# FET-module.net
KiCad netlist of a schematic drawn in Altium Designer
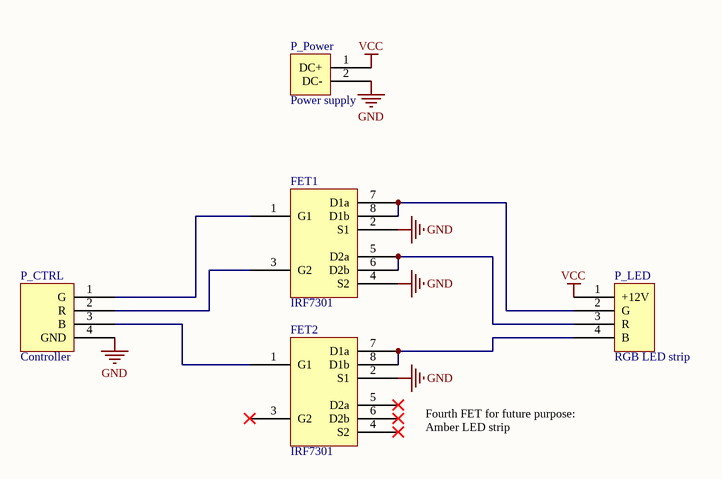
[diagram p0: FET-module.SchDoc]

(export (version "E")
  (design (tool "Eeschema 10.0.6"))
  (components
    (comp (ref "FET1") (value "IRF7301") (footprint "SOIC8") (libsource (lib "FET-module") (part "IRF7301")))
    (comp (ref "FET2") (value "IRF7301") (footprint "SOIC8") (libsource (lib "FET-module") (part "IRF7301")))
    (comp (ref "P_CTRL")
      (value "Controller")
      (footprint "Controller connector")
      (libsource (lib "FET-module") (part "Controller"))
    )
    (comp (ref "P_LED")
      (value "RGB LED strip")
      (footprint "LED strip RGB connector")
      (libsource (lib "FET-module") (part "RGB LED strip"))
    )
    (comp (ref "P_Power")
      (value "Power supply")
      (footprint "DC connector")
      (libsource (lib "FET-module") (part "Power supply"))
    )
  )
  (nets
    (net (code "1") (name "GND") (class "Default")
      (node (ref "FET1") (pin "2") (pinfunction "S1_2") (pintype "passive"))
      (node (ref "FET1") (pin "4") (pinfunction "S2_4") (pintype "passive"))
      (node (ref "FET2") (pin "2") (pinfunction "S1_2") (pintype "passive"))
      (node (ref "P_CTRL") (pin "4") (pinfunction "GND_4") (pintype "passive"))
      (node (ref "P_Power") (pin "2") (pinfunction "DC-_2") (pintype "passive"))
    )
    (net (code "2") (name "Net-(FET1-D1a)") (class "Default")
      (node (ref "FET1") (pin "7") (pinfunction "D1a_7") (pintype "passive"))
      (node (ref "FET1") (pin "8") (pinfunction "D1b_8") (pintype "passive"))
      (node (ref "P_LED") (pin "2") (pinfunction "G_2") (pintype "passive"))
    )
    (net (code "3") (name "Net-(FET1-D2a)") (class "Default")
      (node (ref "FET1") (pin "5") (pinfunction "D2a_5") (pintype "passive"))
      (node (ref "FET1") (pin "6") (pinfunction "D2b_6") (pintype "passive"))
      (node (ref "P_LED") (pin "3") (pinfunction "R_3") (pintype "passive"))
    )
    (net (code "4") (name "Net-(FET1-G1)") (class "Default")
      (node (ref "FET1") (pin "1") (pinfunction "G1_1") (pintype "passive"))
      (node (ref "P_CTRL") (pin "1") (pinfunction "G_1") (pintype "passive"))
    )
    (net (code "5") (name "Net-(FET1-G2)") (class "Default")
      (node (ref "FET1") (pin "3") (pinfunction "G2_3") (pintype "passive"))
      (node (ref "P_CTRL") (pin "2") (pinfunction "R_2") (pintype "passive"))
    )
    (net (code "6") (name "Net-(FET2-D1a)") (class "Default")
      (node (ref "FET2") (pin "7") (pinfunction "D1a_7") (pintype "passive"))
      (node (ref "FET2") (pin "8") (pinfunction "D1b_8") (pintype "passive"))
      (node (ref "P_LED") (pin "4") (pinfunction "B_4") (pintype "passive"))
    )
    (net (code "7") (name "Net-(FET2-G1)") (class "Default")
      (node (ref "FET2") (pin "1") (pinfunction "G1_1") (pintype "passive"))
      (node (ref "P_CTRL") (pin "3") (pinfunction "B_3") (pintype "passive"))
    )
    (net (code "8") (name "VCC") (class "Default")
      (node (ref "P_LED") (pin "1") (pinfunction "+12V_1") (pintype "passive"))
      (node (ref "P_Power") (pin "1") (pinfunction "DC+_1") (pintype "passive"))
    )
    (net (code "9") (name "unconnected-(FET2-D2a-Pad5)") (class "Default")
      (node (ref "FET2") (pin "5") (pinfunction "D2a_5") (pintype "passive+no_connect"))
    )
    (net (code "10") (name "unconnected-(FET2-D2b-Pad6)") (class "Default")
      (node (ref "FET2") (pin "6") (pinfunction "D2b_6") (pintype "passive+no_connect"))
    )
    (net (code "11") (name "unconnected-(FET2-G2-Pad3)") (class "Default")
      (node (ref "FET2") (pin "3") (pinfunction "G2_3") (pintype "passive+no_connect"))
    )
    (net (code "12") (name "unconnected-(FET2-S2-Pad4)") (class "Default")
      (node (ref "FET2") (pin "4") (pinfunction "S2_4") (pintype "passive+no_connect"))
    )
  )
)
